# uc4h_node_v2011.net
KiCad netlist of a schematic drawn in EAGLE
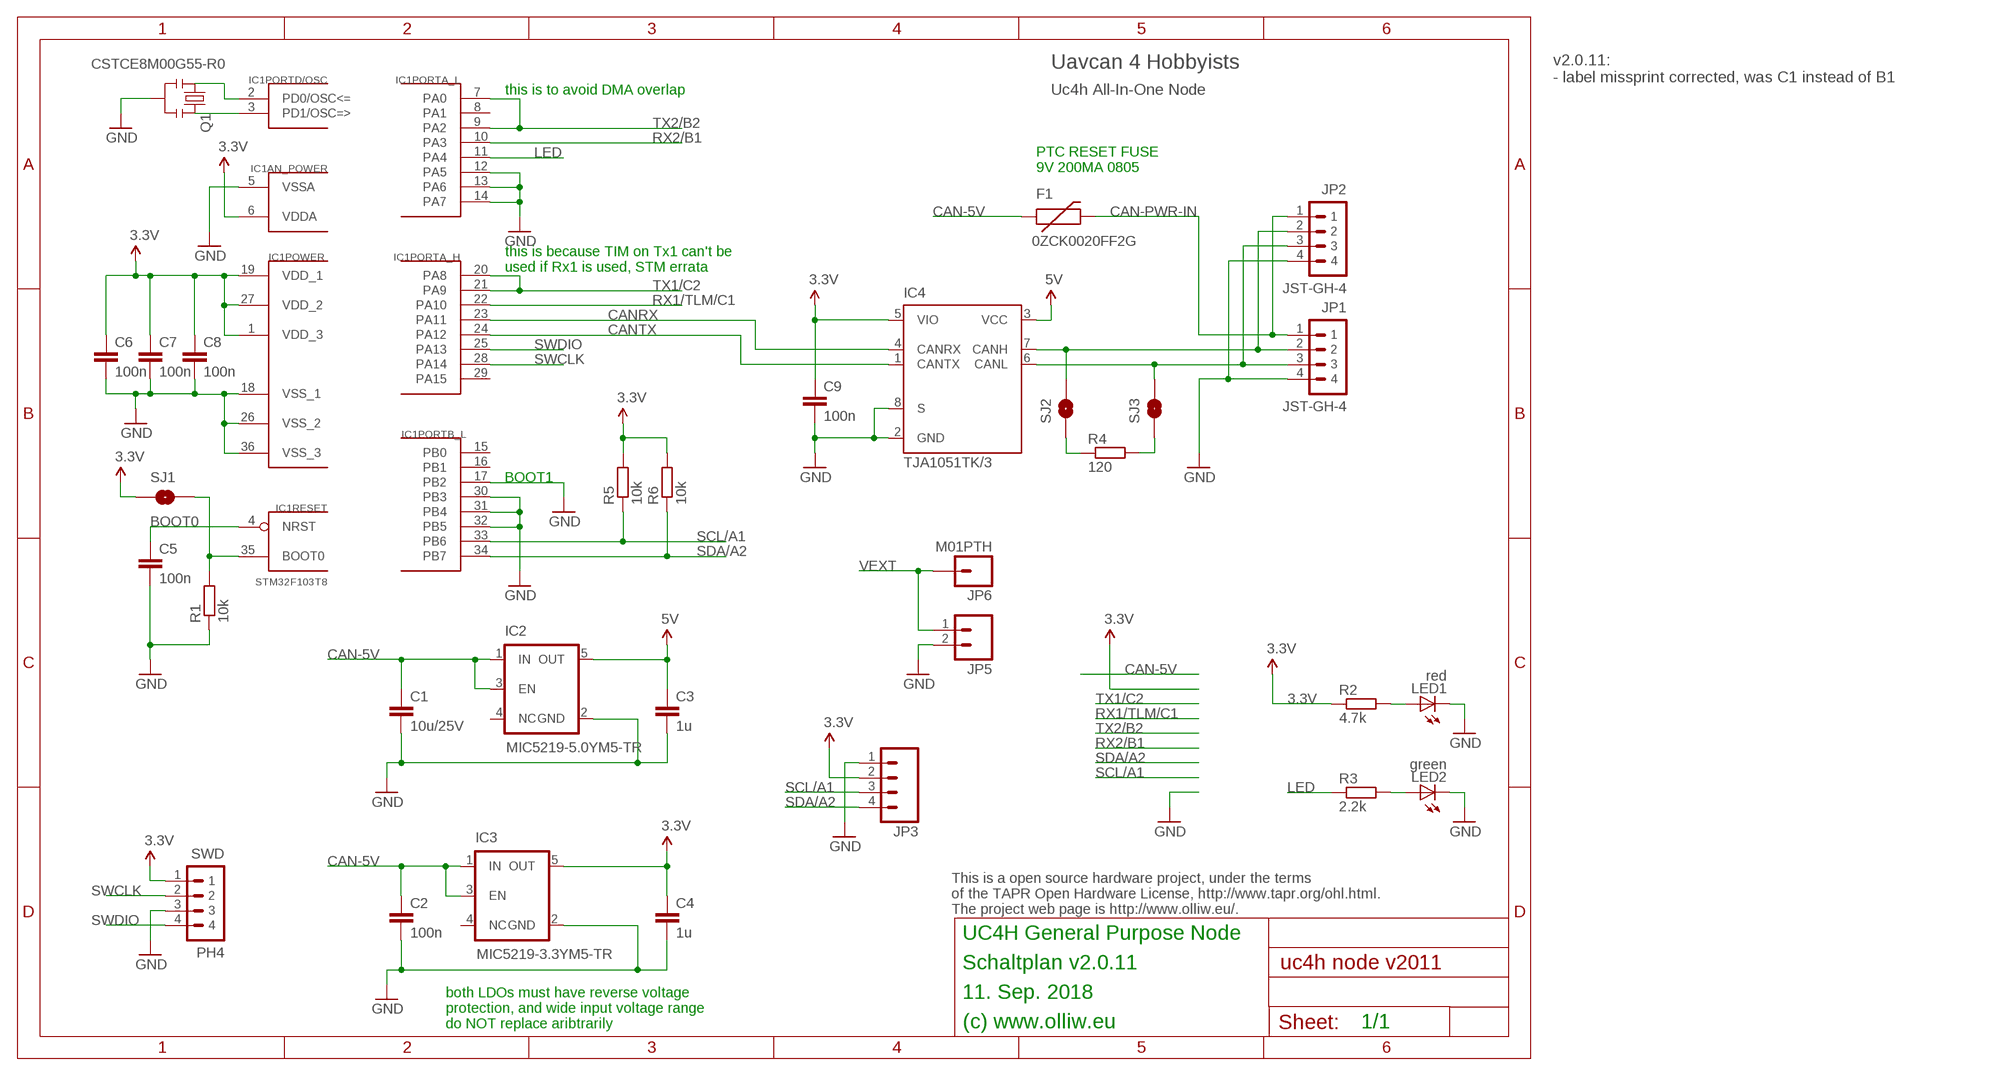
[diagram p0: schematic, sheet 1]

(export (version "E")
  (design (tool "Eeschema 10.0.6"))
  (components
    (comp (ref "C1")
      (value "10u/25V")
      (footprint "eagle-import:C1206")
      (libsource (lib "eagle-import") (part "C-EUC1206"))
    )
    (comp (ref "C2")
      (value "100n")
      (footprint "eagle-import:C0603K")
      (libsource (lib "eagle-import") (part "C-EUC0603K"))
    )
    (comp (ref "C3")
      (value "1u")
      (footprint "eagle-import:C0603K")
      (libsource (lib "eagle-import") (part "C-EUC0603K"))
    )
    (comp (ref "C4")
      (value "1u")
      (footprint "eagle-import:C0603K")
      (libsource (lib "eagle-import") (part "C-EUC0603K"))
    )
    (comp (ref "C5")
      (value "100n")
      (footprint "eagle-import:C0603K")
      (libsource (lib "eagle-import") (part "C-EUC0603K"))
    )
    (comp (ref "C6")
      (value "100n")
      (footprint "eagle-import:C0603K")
      (libsource (lib "eagle-import") (part "C-EUC0603K"))
    )
    (comp (ref "C7")
      (value "100n")
      (footprint "eagle-import:C0603K")
      (libsource (lib "eagle-import") (part "C-EUC0603K"))
    )
    (comp (ref "C8")
      (value "100n")
      (footprint "eagle-import:C0603K")
      (libsource (lib "eagle-import") (part "C-EUC0603K"))
    )
    (comp (ref "C9")
      (value "100n")
      (footprint "eagle-import:C0603K")
      (libsource (lib "eagle-import") (part "C-EUC0603K"))
    )
    (comp (ref "F1")
      (value "0ZCK0020FF2G")
      (footprint "eagle-import:FUSE-0805")
      (libsource (lib "eagle-import") (part "FUSE-PTCFUSE-0805"))
    )
    (comp (ref "IC1")
      (value "STM32F103T8")
      (footprint "eagle-import:VFQFPN36")
      (libsource (lib "eagle-import") (part "STM32F10XTXU6"))
    )
    (comp (ref "IC2")
      (value "MIC5219-5.0YM5-TR")
      (footprint "eagle-import:SOT23-5")
      (libsource (lib "eagle-import") (part "V_REG_TPS76433SOT23-5"))
    )
    (comp (ref "IC3")
      (value "MIC5219-3.3YM5-TR")
      (footprint "eagle-import:SOT23-5")
      (libsource (lib "eagle-import") (part "V_REG_TPS76433SOT23-5"))
    )
    (comp (ref "IC4")
      (value "TJA1051TK/3")
      (footprint "eagle-import:HVSON8")
      (libsource (lib "eagle-import") (part "TJA1051TK/3"))
    )
    (comp (ref "JP1")
      (value "JST-GH-4")
      (footprint "eagle-import:SM04B-GHS-TB")
      (libsource (lib "eagle-import") (part "JST-GH-4"))
    )
    (comp (ref "JP2")
      (value "JST-GH-4")
      (footprint "eagle-import:SM04B-GHS-TB")
      (libsource (lib "eagle-import") (part "JST-GH-4"))
    )
    (comp (ref "JP3")
      (value "M04PTH")
      (footprint "eagle-import:1X04")
      (libsource (lib "eagle-import") (part "M04PTH"))
    )
    (comp (ref "JP5")
      (value "M02PTH")
      (footprint "eagle-import:1X02")
      (libsource (lib "eagle-import") (part "M02PTH"))
    )
    (comp (ref "JP6")
      (value "M01PTH")
      (footprint "eagle-import:1X01")
      (libsource (lib "eagle-import") (part "M01PTH"))
    )
    (comp (ref "LED1")
      (value "red")
      (footprint "eagle-import:CHIPLED_0603")
      (libsource (lib "eagle-import") (part "LEDCHIPLED_0603"))
    )
    (comp (ref "LED2")
      (value "green")
      (footprint "eagle-import:CHIPLED_0603")
      (libsource (lib "eagle-import") (part "LEDCHIPLED_0603"))
    )
    (comp (ref "Q1")
      (value "CSTCE8M00G55-R0")
      (footprint "eagle-import:RESONATOR-SMD")
      (libsource (lib "eagle-import") (part "RESONATORSMD"))
    )
    (comp (ref "R1")
      (value "10k")
      (footprint "eagle-import:R0603")
      (libsource (lib "eagle-import") (part "R-EU_R0603"))
    )
    (comp (ref "R2")
      (value "4.7k")
      (footprint "eagle-import:R0603")
      (libsource (lib "eagle-import") (part "R-EU_R0603"))
    )
    (comp (ref "R3")
      (value "2.2k")
      (footprint "eagle-import:R0603")
      (libsource (lib "eagle-import") (part "R-EU_R0603"))
    )
    (comp (ref "R4")
      (value "120")
      (footprint "eagle-import:R0603")
      (libsource (lib "eagle-import") (part "R-EU_R0603"))
    )
    (comp (ref "R5")
      (value "10k")
      (footprint "eagle-import:R0603")
      (libsource (lib "eagle-import") (part "R-EU_R0603"))
    )
    (comp (ref "R6")
      (value "10k")
      (footprint "eagle-import:R0603")
      (libsource (lib "eagle-import") (part "R-EU_R0603"))
    )
    (comp (ref "SJ1")
      (value "BOOT0")
      (footprint "eagle-import:SJ_2S-NO")
      (libsource (lib "eagle-import") (part "SOLDERJUMPERNO"))
    )
    (comp (ref "SJ2")
      (value "SOLDERJUMPERNO")
      (footprint "eagle-import:SJ_2S-NO")
      (libsource (lib "eagle-import") (part "SOLDERJUMPERNO"))
    )
    (comp (ref "SJ3")
      (value "SOLDERJUMPERNO")
      (footprint "eagle-import:SJ_2S-NO")
      (libsource (lib "eagle-import") (part "SOLDERJUMPERNO"))
    )
    (comp (ref "SWD")
      (value "PH4")
      (footprint "eagle-import:4X1_1P27_OCT_BILEX")
      (libsource (lib "eagle-import") (part "P4X1_1P27-OCT_BILEX"))
    )
  )
  (nets
    (net (code "1") (name "/CAN-5V") (class "Default")
      (node (ref "C1") (pin "1") (pinfunction "1_1") (pintype "passive"))
      (node (ref "C2") (pin "1") (pinfunction "1_1") (pintype "passive"))
      (node (ref "F1") (pin "1") (pinfunction "1_1") (pintype "bidirectional"))
      (node (ref "IC2") (pin "1") (pinfunction "IN_1") (pintype "power_in"))
      (node (ref "IC2") (pin "3") (pinfunction "EN_3") (pintype "input"))
      (node (ref "IC3") (pin "1") (pinfunction "IN_1") (pintype "power_in"))
      (node (ref "IC3") (pin "3") (pinfunction "EN_3") (pintype "input"))
    )
    (net (code "2") (name "/CAN-PWR-IN") (class "Default")
      (node (ref "F1") (pin "2") (pinfunction "2_2") (pintype "bidirectional"))
      (node (ref "JP1") (pin "1") (pinfunction "1_1") (pintype "passive"))
      (node (ref "JP2") (pin "1") (pinfunction "1_1") (pintype "passive"))
    )
    (net (code "3") (name "/CANRX") (class "Default")
      (node (ref "IC1") (pin "23") (pinfunction "PA11_23") (pintype "bidirectional"))
      (node (ref "IC4") (pin "4") (pinfunction "CANRX_4") (pintype "output"))
    )
    (net (code "4") (name "/CANTX") (class "Default")
      (node (ref "IC1") (pin "24") (pinfunction "PA12_24") (pintype "bidirectional"))
      (node (ref "IC4") (pin "1") (pinfunction "CANTX_1") (pintype "input"))
    )
    (net (code "5") (name "/LED") (class "Default")
      (node (ref "IC1") (pin "11") (pinfunction "PA4_11") (pintype "bidirectional"))
      (node (ref "R3") (pin "1") (pinfunction "1_1") (pintype "passive"))
    )
    (net (code "6") (name "/RX1{slash}TLM{slash}C1") (class "Default")
      (node (ref "IC1") (pin "22") (pinfunction "PA10_22") (pintype "bidirectional"))
    )
    (net (code "7") (name "/RX2{slash}B1") (class "Default")
      (node (ref "IC1") (pin "10") (pinfunction "PA3_10") (pintype "bidirectional"))
    )
    (net (code "8") (name "/SCL{slash}A1") (class "Default")
      (node (ref "IC1") (pin "33") (pinfunction "PB6_33") (pintype "bidirectional"))
      (node (ref "JP3") (pin "3") (pinfunction "3_3") (pintype "passive"))
      (node (ref "R5") (pin "1") (pinfunction "1_1") (pintype "passive"))
    )
    (net (code "9") (name "/SDA{slash}A2") (class "Default")
      (node (ref "IC1") (pin "34") (pinfunction "PB7_34") (pintype "bidirectional"))
      (node (ref "JP3") (pin "4") (pinfunction "4_4") (pintype "passive"))
      (node (ref "R6") (pin "1") (pinfunction "1_1") (pintype "passive"))
    )
    (net (code "10") (name "/SWCLK") (class "Default")
      (node (ref "IC1") (pin "28") (pinfunction "PA14_28") (pintype "bidirectional"))
      (node (ref "SWD") (pin "2") (pinfunction "2_2") (pintype "passive"))
    )
    (net (code "11") (name "/SWDIO") (class "Default")
      (node (ref "IC1") (pin "25") (pinfunction "PA13_25") (pintype "bidirectional"))
      (node (ref "SWD") (pin "4") (pinfunction "4_4") (pintype "passive"))
    )
    (net (code "12") (name "/TX1{slash}C2") (class "Default")
      (node (ref "IC1") (pin "20") (pinfunction "PA8_20") (pintype "bidirectional"))
      (node (ref "IC1") (pin "21") (pinfunction "PA9_21") (pintype "bidirectional"))
    )
    (net (code "13") (name "/TX2{slash}B2") (class "Default")
      (node (ref "IC1") (pin "7") (pinfunction "PA0_7") (pintype "bidirectional"))
      (node (ref "IC1") (pin "9") (pinfunction "PA2_9") (pintype "bidirectional"))
    )
    (net (code "14") (name "/VEXT") (class "Default")
      (node (ref "JP5") (pin "1") (pinfunction "1_1") (pintype "passive"))
      (node (ref "JP6") (pin "1") (pinfunction "1_1") (pintype "passive"))
    )
    (net (code "15") (name "3.3V") (class "Default")
      (node (ref "C4") (pin "1") (pinfunction "1_1") (pintype "passive"))
      (node (ref "C6") (pin "1") (pinfunction "1_1") (pintype "passive"))
      (node (ref "C7") (pin "1") (pinfunction "1_1") (pintype "passive"))
      (node (ref "C8") (pin "1") (pinfunction "1_1") (pintype "passive"))
      (node (ref "C9") (pin "1") (pinfunction "1_1") (pintype "passive"))
      (node (ref "IC1") (pin "1") (pinfunction "VDD_3_1") (pintype "power_in"))
      (node (ref "IC1") (pin "19") (pinfunction "VDD_1_19") (pintype "power_in"))
      (node (ref "IC1") (pin "27") (pinfunction "VDD_2_27") (pintype "power_in"))
      (node (ref "IC1") (pin "6") (pinfunction "VDDA_6") (pintype "power_in"))
      (node (ref "IC3") (pin "5") (pinfunction "OUT_5") (pintype "output"))
      (node (ref "IC4") (pin "5") (pinfunction "VIO_5") (pintype "power_in"))
      (node (ref "JP3") (pin "2") (pinfunction "2_2") (pintype "passive"))
      (node (ref "R2") (pin "1") (pinfunction "1_1") (pintype "passive"))
      (node (ref "R5") (pin "2") (pinfunction "2_2") (pintype "passive"))
      (node (ref "R6") (pin "2") (pinfunction "2_2") (pintype "passive"))
      (node (ref "SJ1") (pin "1") (pinfunction "1_1") (pintype "passive"))
      (node (ref "SWD") (pin "1") (pinfunction "1_1") (pintype "passive"))
    )
    (net (code "16") (name "5V") (class "Default")
      (node (ref "C3") (pin "1") (pinfunction "1_1") (pintype "passive"))
      (node (ref "IC2") (pin "5") (pinfunction "OUT_5") (pintype "output"))
      (node (ref "IC4") (pin "3") (pinfunction "VCC_3") (pintype "power_in"))
    )
    (net (code "17") (name "GND") (class "Default")
      (node (ref "C1") (pin "2") (pinfunction "2_2") (pintype "passive"))
      (node (ref "C2") (pin "2") (pinfunction "2_2") (pintype "passive"))
      (node (ref "C3") (pin "2") (pinfunction "2_2") (pintype "passive"))
      (node (ref "C4") (pin "2") (pinfunction "2_2") (pintype "passive"))
      (node (ref "C5") (pin "2") (pinfunction "2_2") (pintype "passive"))
      (node (ref "C6") (pin "2") (pinfunction "2_2") (pintype "passive"))
      (node (ref "C7") (pin "2") (pinfunction "2_2") (pintype "passive"))
      (node (ref "C8") (pin "2") (pinfunction "2_2") (pintype "passive"))
      (node (ref "C9") (pin "2") (pinfunction "2_2") (pintype "passive"))
      (node (ref "IC1") (pin "12") (pinfunction "PA5_12") (pintype "bidirectional"))
      (node (ref "IC1") (pin "13") (pinfunction "PA6_13") (pintype "bidirectional"))
      (node (ref "IC1") (pin "14") (pinfunction "PA7_14") (pintype "bidirectional"))
      (node (ref "IC1") (pin "17") (pinfunction "PB2_17") (pintype "bidirectional"))
      (node (ref "IC1") (pin "18") (pinfunction "VSS_1_18") (pintype "power_in"))
      (node (ref "IC1") (pin "26") (pinfunction "VSS_2_26") (pintype "power_in"))
      (node (ref "IC1") (pin "30") (pinfunction "PB3_30") (pintype "bidirectional"))
      (node (ref "IC1") (pin "31") (pinfunction "PB4_31") (pintype "bidirectional"))
      (node (ref "IC1") (pin "32") (pinfunction "PB5_32") (pintype "bidirectional"))
      (node (ref "IC1") (pin "36") (pinfunction "VSS_3_36") (pintype "power_in"))
      (node (ref "IC1") (pin "5") (pinfunction "VSSA_5") (pintype "power_in"))
      (node (ref "IC2") (pin "2") (pinfunction "GND_2") (pintype "power_in"))
      (node (ref "IC3") (pin "2") (pinfunction "GND_2") (pintype "power_in"))
      (node (ref "IC4") (pin "2") (pinfunction "GND_2") (pintype "power_in"))
      (node (ref "IC4") (pin "8") (pinfunction "S_8") (pintype "input"))
      (node (ref "JP1") (pin "4") (pinfunction "4_4") (pintype "passive"))
      (node (ref "JP2") (pin "4") (pinfunction "4_4") (pintype "passive"))
      (node (ref "JP3") (pin "1") (pinfunction "1_1") (pintype "passive"))
      (node (ref "JP5") (pin "2") (pinfunction "2_2") (pintype "passive"))
      (node (ref "LED1") (pin "C") (pinfunction "C_C") (pintype "passive"))
      (node (ref "LED2") (pin "C") (pinfunction "C_C") (pintype "passive"))
      (node (ref "Q1") (pin "2") (pinfunction "2_2") (pintype "passive"))
      (node (ref "R1") (pin "1") (pinfunction "1_1") (pintype "passive"))
      (node (ref "SWD") (pin "3") (pinfunction "3_3") (pintype "passive"))
    )
    (net (code "18") (name "Net-(IC1E-PD0{slash}OSC<=)") (class "Default")
      (node (ref "IC1") (pin "2") (pinfunction "PD0/OSC<=_2") (pintype "bidirectional"))
      (node (ref "Q1") (pin "1") (pinfunction "1_1") (pintype "passive"))
    )
    (net (code "19") (name "Net-(IC1E-PD1{slash}OSC=>)") (class "Default")
      (node (ref "IC1") (pin "3") (pinfunction "PD1/OSC=>_3") (pintype "bidirectional"))
      (node (ref "Q1") (pin "3") (pinfunction "3_3") (pintype "passive"))
    )
    (net (code "20") (name "Net-(IC1G-BOOT0)") (class "Default")
      (node (ref "IC1") (pin "35") (pinfunction "BOOT0_35") (pintype "input"))
      (node (ref "R1") (pin "2") (pinfunction "2_2") (pintype "passive"))
      (node (ref "SJ1") (pin "2") (pinfunction "2_2") (pintype "passive"))
    )
    (net (code "21") (name "Net-(IC1G-NRST)") (class "Default")
      (node (ref "C5") (pin "1") (pinfunction "1_1") (pintype "passive"))
      (node (ref "IC1") (pin "4") (pinfunction "NRST_4") (pintype "input"))
    )
    (net (code "22") (name "Net-(IC4-CANH)") (class "Default")
      (node (ref "IC4") (pin "7") (pinfunction "CANH_7") (pintype "bidirectional"))
      (node (ref "JP1") (pin "2") (pinfunction "2_2") (pintype "passive"))
      (node (ref "JP2") (pin "2") (pinfunction "2_2") (pintype "passive"))
      (node (ref "SJ2") (pin "2") (pinfunction "2_2") (pintype "passive"))
    )
    (net (code "23") (name "Net-(IC4-CANL)") (class "Default")
      (node (ref "IC4") (pin "6") (pinfunction "CANL_6") (pintype "bidirectional"))
      (node (ref "JP1") (pin "3") (pinfunction "3_3") (pintype "passive"))
      (node (ref "JP2") (pin "3") (pinfunction "3_3") (pintype "passive"))
      (node (ref "SJ3") (pin "2") (pinfunction "2_2") (pintype "passive"))
    )
    (net (code "24") (name "Net-(LED1-PadA)") (class "Default")
      (node (ref "LED1") (pin "A") (pinfunction "A_A") (pintype "passive"))
      (node (ref "R2") (pin "2") (pinfunction "2_2") (pintype "passive"))
    )
    (net (code "25") (name "Net-(LED2-PadA)") (class "Default")
      (node (ref "LED2") (pin "A") (pinfunction "A_A") (pintype "passive"))
      (node (ref "R3") (pin "2") (pinfunction "2_2") (pintype "passive"))
    )
    (net (code "26") (name "Net-(R4-Pad1)") (class "Default")
      (node (ref "R4") (pin "1") (pinfunction "1_1") (pintype "passive"))
      (node (ref "SJ2") (pin "1") (pinfunction "1_1") (pintype "passive"))
    )
    (net (code "27") (name "Net-(R4-Pad2)") (class "Default")
      (node (ref "R4") (pin "2") (pinfunction "2_2") (pintype "passive"))
      (node (ref "SJ3") (pin "1") (pinfunction "1_1") (pintype "passive"))
    )
    (net (code "28") (name "unconnected-(IC1B-PA15-Pad29)") (class "Default")
      (node (ref "IC1") (pin "29") (pinfunction "PA15_29") (pintype "bidirectional"))
    )
    (net (code "29") (name "unconnected-(IC1C-PA1-Pad8)") (class "Default")
      (node (ref "IC1") (pin "8") (pinfunction "PA1_8") (pintype "bidirectional"))
    )
    (net (code "30") (name "unconnected-(IC1D-PB0-Pad15)") (class "Default")
      (node (ref "IC1") (pin "15") (pinfunction "PB0_15") (pintype "bidirectional"))
    )
    (net (code "31") (name "unconnected-(IC1D-PB1-Pad16)") (class "Default")
      (node (ref "IC1") (pin "16") (pinfunction "PB1_16") (pintype "bidirectional"))
    )
    (net (code "32") (name "unconnected-(IC2-NC-Pad4)") (class "Default")
      (node (ref "IC2") (pin "4") (pinfunction "NC_4") (pintype "passive"))
    )
    (net (code "33") (name "unconnected-(IC3-NC-Pad4)") (class "Default")
      (node (ref "IC3") (pin "4") (pinfunction "NC_4") (pintype "passive"))
    )
  )
)
